# STM8L_Remote_Schematic.net
KiCad netlist of a schematic drawn in Altium Designer
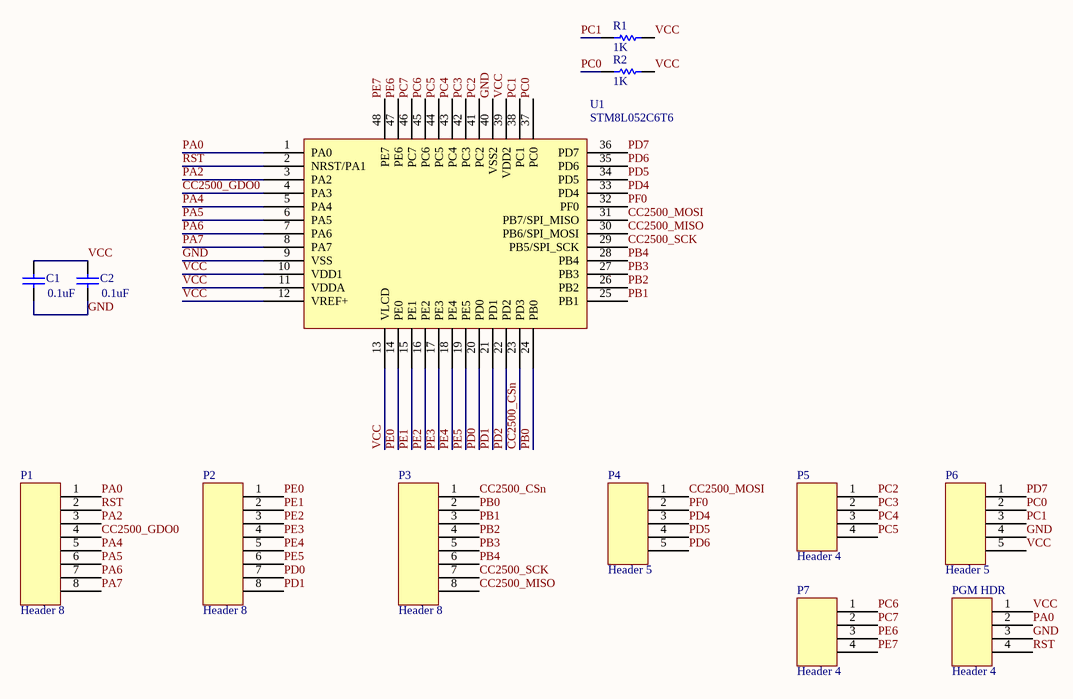
[diagram p0: STM8L Remote Schematic.SchDoc]

(export (version "E")
  (design (tool "Eeschema 10.0.6"))
  (components
    (comp (ref "C1")
      (value "0.1uF")
      (footprint "0805")
      (description "Ceramic Chip Capacitor - Standard")
      (fields (field (name "PUBLISHER") "Altium Limited"))
      (libsource (lib "KEMET Chip Capacitor") (part "C0805"))
    )
    (comp (ref "C2")
      (value "0.1uF")
      (footprint "0805")
      (description "Ceramic Chip Capacitor - Standard")
      (fields (field (name "PUBLISHER") "Altium Limited"))
      (libsource (lib "KEMET Chip Capacitor") (part "C0805"))
    )
    (comp (ref "P1")
      (value "Header 8")
      (footprint "HEADER 8 W/O BORDER")
      (libsource (lib "2mm Pitch Connector") (part "Header 8"))
    )
    (comp (ref "P2")
      (value "Header 8")
      (footprint "HEADER 8 W/O BORDER")
      (libsource (lib "2mm Pitch Connector") (part "Header 8"))
    )
    (comp (ref "P3")
      (value "Header 8")
      (footprint "HEADER 8 W/O BORDER")
      (libsource (lib "2mm Pitch Connector") (part "Header 8"))
    )
    (comp (ref "P4")
      (value "Header 5")
      (footprint "HEADER 5 W/O BORDER")
      (libsource (lib "2mm Pitch Connector") (part "Header 5"))
    )
    (comp (ref "P5")
      (value "Header 4")
      (footprint "HEADER 4 W/O BORDER")
      (libsource (lib "2mm Pitch Connector") (part "Header 4"))
    )
    (comp (ref "P6")
      (value "Header 5")
      (footprint "HEADER 5 W/O BORDER")
      (libsource (lib "2mm Pitch Connector") (part "Header 5"))
    )
    (comp (ref "P7")
      (value "Header 4")
      (footprint "HEADER 4 W/O BORDER")
      (libsource (lib "2mm Pitch Connector") (part "Header 4"))
    )
    (comp (ref "PGM HDR")
      (value "Header 4")
      (footprint "HEADER 4 W/O BORDER")
      (libsource (lib "2mm Pitch Connector") (part "Header 4"))
    )
    (comp (ref "R1")
      (value "1K")
      (footprint "ERA-0805")
      (fields (field (name "PUBLISHER") "Altium Limited"))
      (libsource (lib "Panasonic Resistor") (part "ERA6Y"))
    )
    (comp (ref "R2")
      (value "1K")
      (footprint "ERA-0805")
      (fields (field (name "PUBLISHER") "Altium Limited"))
      (libsource (lib "Panasonic Resistor") (part "ERA6Y"))
    )
    (comp (ref "U1")
      (value "STM8L052C6T6")
      (footprint "STM8L052C6-SQFP50P900X900X1600-48N")
      (libsource (lib "STM8L052C6") (part "STM8L052C6T6"))
    )
  )
  (nets
    (net (code "1") (name "/CC2500_CSn") (class "Default")
      (node (ref "P3") (pin "1") (pinfunction "1_1") (pintype "passive"))
      (node (ref "U1") (pin "23") (pinfunction "PD3_23") (pintype "passive"))
    )
    (net (code "2") (name "/CC2500_GDO0") (class "Default")
      (node (ref "P1") (pin "4") (pinfunction "4_4") (pintype "passive"))
      (node (ref "U1") (pin "4") (pinfunction "PA3_4") (pintype "passive"))
    )
    (net (code "3") (name "/CC2500_MISO") (class "Default")
      (node (ref "P3") (pin "8") (pinfunction "8_8") (pintype "passive"))
      (node (ref "U1") (pin "30") (pinfunction "PB6/SPI_MOSI_30") (pintype "passive"))
    )
    (net (code "4") (name "/CC2500_MOSI") (class "Default")
      (node (ref "P4") (pin "1") (pinfunction "1_1") (pintype "passive"))
      (node (ref "U1") (pin "31") (pinfunction "PB7/SPI_MISO_31") (pintype "passive"))
    )
    (net (code "5") (name "/CC2500_SCK") (class "Default")
      (node (ref "P3") (pin "7") (pinfunction "7_7") (pintype "passive"))
      (node (ref "U1") (pin "29") (pinfunction "PB5/SPI_SCK_29") (pintype "passive"))
    )
    (net (code "6") (name "/GND") (class "Default")
      (node (ref "C1") (pin "2") (pinfunction "2_2") (pintype "passive"))
      (node (ref "C2") (pin "1") (pinfunction "1_1") (pintype "passive"))
      (node (ref "P6") (pin "4") (pinfunction "4_4") (pintype "passive"))
      (node (ref "PGM HDR") (pin "3") (pinfunction "3_3") (pintype "passive"))
      (node (ref "U1") (pin "40") (pinfunction "VSS2_40") (pintype "passive"))
      (node (ref "U1") (pin "9") (pinfunction "VSS_9") (pintype "passive"))
    )
    (net (code "7") (name "/PA0") (class "Default")
      (node (ref "P1") (pin "1") (pinfunction "1_1") (pintype "passive"))
      (node (ref "PGM HDR") (pin "2") (pinfunction "2_2") (pintype "passive"))
      (node (ref "U1") (pin "1") (pinfunction "PA0_1") (pintype "passive"))
    )
    (net (code "8") (name "/PA2") (class "Default")
      (node (ref "P1") (pin "3") (pinfunction "3_3") (pintype "passive"))
      (node (ref "U1") (pin "3") (pinfunction "PA2_3") (pintype "passive"))
    )
    (net (code "9") (name "/PA4") (class "Default")
      (node (ref "P1") (pin "5") (pinfunction "5_5") (pintype "passive"))
      (node (ref "U1") (pin "5") (pinfunction "PA4_5") (pintype "passive"))
    )
    (net (code "10") (name "/PA5") (class "Default")
      (node (ref "P1") (pin "6") (pinfunction "6_6") (pintype "passive"))
      (node (ref "U1") (pin "6") (pinfunction "PA5_6") (pintype "passive"))
    )
    (net (code "11") (name "/PA6") (class "Default")
      (node (ref "P1") (pin "7") (pinfunction "7_7") (pintype "passive"))
      (node (ref "U1") (pin "7") (pinfunction "PA6_7") (pintype "passive"))
    )
    (net (code "12") (name "/PA7") (class "Default")
      (node (ref "P1") (pin "8") (pinfunction "8_8") (pintype "passive"))
      (node (ref "U1") (pin "8") (pinfunction "PA7_8") (pintype "passive"))
    )
    (net (code "13") (name "/PB0") (class "Default")
      (node (ref "P3") (pin "2") (pinfunction "2_2") (pintype "passive"))
      (node (ref "U1") (pin "24") (pinfunction "PB0_24") (pintype "passive"))
    )
    (net (code "14") (name "/PB1") (class "Default")
      (node (ref "P3") (pin "3") (pinfunction "3_3") (pintype "passive"))
      (node (ref "U1") (pin "25") (pinfunction "PB1_25") (pintype "passive"))
    )
    (net (code "15") (name "/PB2") (class "Default")
      (node (ref "P3") (pin "4") (pinfunction "4_4") (pintype "passive"))
      (node (ref "U1") (pin "26") (pinfunction "PB2_26") (pintype "passive"))
    )
    (net (code "16") (name "/PB3") (class "Default")
      (node (ref "P3") (pin "5") (pinfunction "5_5") (pintype "passive"))
      (node (ref "U1") (pin "27") (pinfunction "PB3_27") (pintype "passive"))
    )
    (net (code "17") (name "/PB4") (class "Default")
      (node (ref "P3") (pin "6") (pinfunction "6_6") (pintype "passive"))
      (node (ref "U1") (pin "28") (pinfunction "PB4_28") (pintype "passive"))
    )
    (net (code "18") (name "/PC0") (class "Default")
      (node (ref "P6") (pin "2") (pinfunction "2_2") (pintype "passive"))
      (node (ref "R2") (pin "1") (pinfunction "1_1") (pintype "passive"))
      (node (ref "U1") (pin "37") (pinfunction "PC0_37") (pintype "passive"))
    )
    (net (code "19") (name "/PC1") (class "Default")
      (node (ref "P6") (pin "3") (pinfunction "3_3") (pintype "passive"))
      (node (ref "R1") (pin "1") (pinfunction "1_1") (pintype "passive"))
      (node (ref "U1") (pin "38") (pinfunction "PC1_38") (pintype "passive"))
    )
    (net (code "20") (name "/PC2") (class "Default")
      (node (ref "P5") (pin "1") (pinfunction "1_1") (pintype "passive"))
      (node (ref "U1") (pin "41") (pinfunction "PC2_41") (pintype "passive"))
    )
    (net (code "21") (name "/PC3") (class "Default")
      (node (ref "P5") (pin "2") (pinfunction "2_2") (pintype "passive"))
      (node (ref "U1") (pin "42") (pinfunction "PC3_42") (pintype "passive"))
    )
    (net (code "22") (name "/PC4") (class "Default")
      (node (ref "P5") (pin "3") (pinfunction "3_3") (pintype "passive"))
      (node (ref "U1") (pin "43") (pinfunction "PC4_43") (pintype "passive"))
    )
    (net (code "23") (name "/PC5") (class "Default")
      (node (ref "P5") (pin "4") (pinfunction "4_4") (pintype "passive"))
      (node (ref "U1") (pin "44") (pinfunction "PC5_44") (pintype "passive"))
    )
    (net (code "24") (name "/PC6") (class "Default")
      (node (ref "P7") (pin "1") (pinfunction "1_1") (pintype "passive"))
      (node (ref "U1") (pin "45") (pinfunction "PC6_45") (pintype "passive"))
    )
    (net (code "25") (name "/PC7") (class "Default")
      (node (ref "P7") (pin "2") (pinfunction "2_2") (pintype "passive"))
      (node (ref "U1") (pin "46") (pinfunction "PC7_46") (pintype "passive"))
    )
    (net (code "26") (name "/PD0") (class "Default")
      (node (ref "P2") (pin "7") (pinfunction "7_7") (pintype "passive"))
      (node (ref "U1") (pin "20") (pinfunction "PD0_20") (pintype "passive"))
    )
    (net (code "27") (name "/PD1") (class "Default")
      (node (ref "P2") (pin "8") (pinfunction "8_8") (pintype "passive"))
      (node (ref "U1") (pin "21") (pinfunction "PD1_21") (pintype "passive"))
    )
    (net (code "28") (name "/PD2") (class "Default")
      (node (ref "U1") (pin "22") (pinfunction "PD2_22") (pintype "passive"))
    )
    (net (code "29") (name "/PD4") (class "Default")
      (node (ref "P4") (pin "3") (pinfunction "3_3") (pintype "passive"))
      (node (ref "U1") (pin "33") (pinfunction "PD4_33") (pintype "passive"))
    )
    (net (code "30") (name "/PD5") (class "Default")
      (node (ref "P4") (pin "4") (pinfunction "4_4") (pintype "passive"))
      (node (ref "U1") (pin "34") (pinfunction "PD5_34") (pintype "passive"))
    )
    (net (code "31") (name "/PD6") (class "Default")
      (node (ref "P4") (pin "5") (pinfunction "5_5") (pintype "passive"))
      (node (ref "U1") (pin "35") (pinfunction "PD6_35") (pintype "passive"))
    )
    (net (code "32") (name "/PD7") (class "Default")
      (node (ref "P6") (pin "1") (pinfunction "1_1") (pintype "passive"))
      (node (ref "U1") (pin "36") (pinfunction "PD7_36") (pintype "passive"))
    )
    (net (code "33") (name "/PE0") (class "Default")
      (node (ref "P2") (pin "1") (pinfunction "1_1") (pintype "passive"))
      (node (ref "U1") (pin "14") (pinfunction "PE0_14") (pintype "passive"))
    )
    (net (code "34") (name "/PE1") (class "Default")
      (node (ref "P2") (pin "2") (pinfunction "2_2") (pintype "passive"))
      (node (ref "U1") (pin "15") (pinfunction "PE1_15") (pintype "passive"))
    )
    (net (code "35") (name "/PE2") (class "Default")
      (node (ref "P2") (pin "3") (pinfunction "3_3") (pintype "passive"))
      (node (ref "U1") (pin "16") (pinfunction "PE2_16") (pintype "passive"))
    )
    (net (code "36") (name "/PE3") (class "Default")
      (node (ref "P2") (pin "4") (pinfunction "4_4") (pintype "passive"))
      (node (ref "U1") (pin "17") (pinfunction "PE3_17") (pintype "passive"))
    )
    (net (code "37") (name "/PE4") (class "Default")
      (node (ref "P2") (pin "5") (pinfunction "5_5") (pintype "passive"))
      (node (ref "U1") (pin "18") (pinfunction "PE4_18") (pintype "passive"))
    )
    (net (code "38") (name "/PE5") (class "Default")
      (node (ref "P2") (pin "6") (pinfunction "6_6") (pintype "passive"))
      (node (ref "U1") (pin "19") (pinfunction "PE5_19") (pintype "passive"))
    )
    (net (code "39") (name "/PE6") (class "Default")
      (node (ref "P7") (pin "3") (pinfunction "3_3") (pintype "passive"))
      (node (ref "U1") (pin "47") (pinfunction "PE6_47") (pintype "passive"))
    )
    (net (code "40") (name "/PE7") (class "Default")
      (node (ref "P7") (pin "4") (pinfunction "4_4") (pintype "passive"))
      (node (ref "U1") (pin "48") (pinfunction "PE7_48") (pintype "passive"))
    )
    (net (code "41") (name "/PF0") (class "Default")
      (node (ref "P4") (pin "2") (pinfunction "2_2") (pintype "passive"))
      (node (ref "U1") (pin "32") (pinfunction "PF0_32") (pintype "passive"))
    )
    (net (code "42") (name "/RST") (class "Default")
      (node (ref "P1") (pin "2") (pinfunction "2_2") (pintype "passive"))
      (node (ref "PGM HDR") (pin "4") (pinfunction "4_4") (pintype "passive"))
      (node (ref "U1") (pin "2") (pinfunction "NRST/PA1_2") (pintype "passive"))
    )
    (net (code "43") (name "/VCC") (class "Default")
      (node (ref "C1") (pin "1") (pinfunction "1_1") (pintype "passive"))
      (node (ref "C2") (pin "2") (pinfunction "2_2") (pintype "passive"))
      (node (ref "P6") (pin "5") (pinfunction "5_5") (pintype "passive"))
      (node (ref "PGM HDR") (pin "1") (pinfunction "1_1") (pintype "passive"))
      (node (ref "R1") (pin "2") (pinfunction "2_2") (pintype "passive"))
      (node (ref "R2") (pin "2") (pinfunction "2_2") (pintype "passive"))
      (node (ref "U1") (pin "10") (pinfunction "VDD1_10") (pintype "passive"))
      (node (ref "U1") (pin "11") (pinfunction "VDDA_11") (pintype "passive"))
      (node (ref "U1") (pin "12") (pinfunction "VREF+_12") (pintype "passive"))
      (node (ref "U1") (pin "13") (pinfunction "VLCD_13") (pintype "passive"))
      (node (ref "U1") (pin "39") (pinfunction "VDD2_39") (pintype "passive"))
    )
  )
)
